# USB.net
KiCad netlist of a schematic drawn in Altium Designer
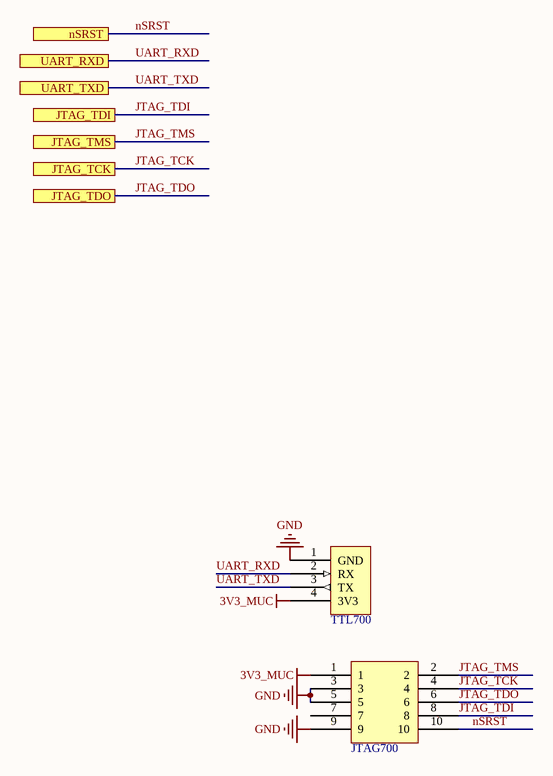
[diagram p0: USB.SchDoc]

(export (version "E")
  (design (tool "Eeschema 10.0.6"))
  (components
    (comp (ref "JTAG700")
      (value "SHF-105-01-L-D-TH")
      (footprint "SHF-105-01-L-D-TH")
      (description "Samtex 2x5pol; THT 1.27mm")
      (fields (field (name "PART NUMBER") "Samtec SHF-105-01-L-D-TH"))
      (libsource (lib "Symeo_libs") (part "CLM-105-02-L-D"))
    )
    (comp (ref "TTL700")
      (value "RS232 Conector TTL")
      (footprint "HDR1X4")
      (description "Stiftleiste; RM:2.54mm; 4 polig einreihig, powered")
      (fields (field (name "PART NUMBER") "Connector - RS232 Conector TTL powered"))
      (libsource (lib "Symeo_libs") (part "RS232_TTL_Power"))
    )
  )
  (nets
    (net (code "1") (name "/JTAG_TCK") (class "Default")
      (node (ref "JTAG700") (pin "4") (pinfunction "4_4") (pintype "passive"))
    )
    (net (code "2") (name "/JTAG_TDI") (class "Default")
      (node (ref "JTAG700") (pin "8") (pinfunction "8_8") (pintype "passive"))
    )
    (net (code "3") (name "/JTAG_TDO") (class "Default")
      (node (ref "JTAG700") (pin "6") (pinfunction "6_6") (pintype "passive"))
    )
    (net (code "4") (name "/JTAG_TMS") (class "Default")
      (node (ref "JTAG700") (pin "2") (pinfunction "2_2") (pintype "passive"))
    )
    (net (code "5") (name "/UART_RXD") (class "Default")
      (node (ref "TTL700") (pin "2") (pinfunction "RX_2") (pintype "input"))
    )
    (net (code "6") (name "/UART_TXD") (class "Default")
      (node (ref "TTL700") (pin "3") (pinfunction "TX_3") (pintype "output"))
    )
    (net (code "7") (name "/nSRST") (class "Default")
      (node (ref "JTAG700") (pin "10") (pinfunction "10_10") (pintype "passive"))
    )
    (net (code "8") (name "3V3_MUC") (class "Default")
      (node (ref "JTAG700") (pin "1") (pinfunction "1_1") (pintype "passive"))
      (node (ref "TTL700") (pin "4") (pinfunction "3V3_4") (pintype "power_in"))
    )
    (net (code "9") (name "GND") (class "Default")
      (node (ref "JTAG700") (pin "3") (pinfunction "3_3") (pintype "passive"))
      (node (ref "JTAG700") (pin "5") (pinfunction "5_5") (pintype "passive"))
      (node (ref "JTAG700") (pin "9") (pinfunction "9_9") (pintype "passive"))
      (node (ref "TTL700") (pin "1") (pinfunction "GND_1") (pintype "power_in"))
    )
    (net (code "10") (name "unconnected-(JTAG700-Pad7)") (class "Default")
      (node (ref "JTAG700") (pin "7") (pinfunction "7_7") (pintype "passive"))
    )
  )
)
